# RP2040.net
KiCad netlist of a schematic drawn in Altium Designer
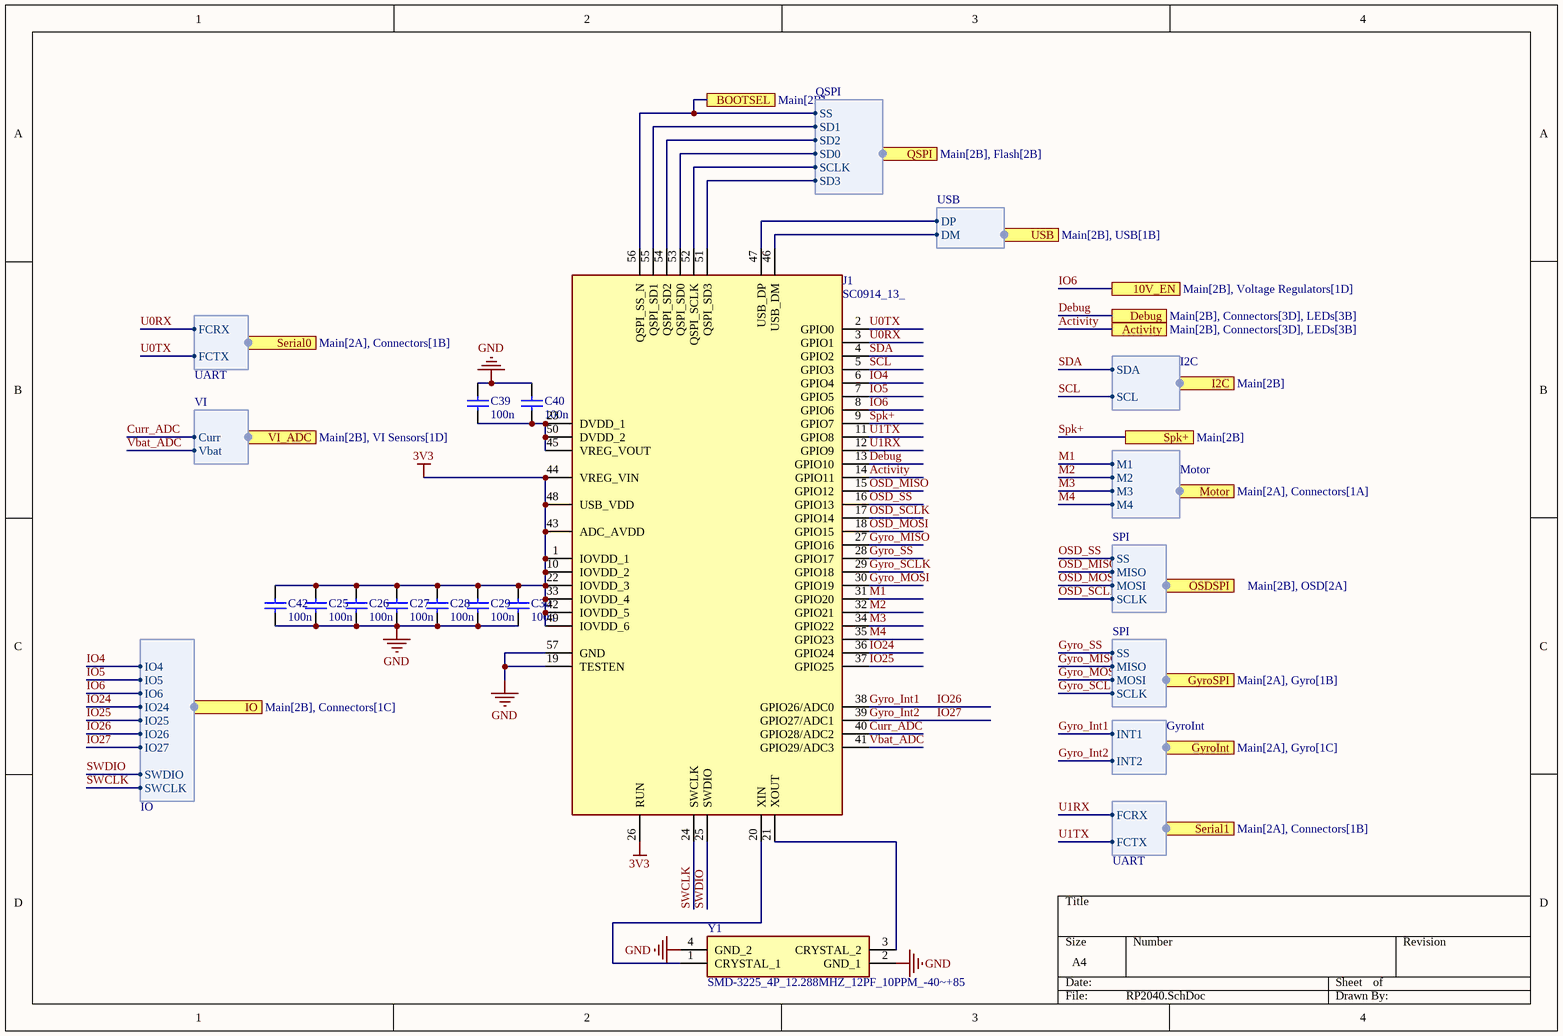
[diagram p0: RP2040.SchDoc]

(export (version "E")
  (design (tool "Eeschema 10.0.6"))
  (components
    (comp (ref "C25")
      (value "100n")
      (footprint "CAPC0603(1608)55_N")
      (description "Keramikvielschichtkondensator, SMD, Baureihe MC, ± 20%")
      (fields (field (name "MANUFACTURER") "Multicomp"))
      (libsource (lib "Standardbauteile") (part "Cap 100n"))
    )
    (comp (ref "C26")
      (value "100n")
      (footprint "CAPC0603(1608)55_N")
      (description "Keramikvielschichtkondensator, SMD, Baureihe MC, ± 20%")
      (fields (field (name "MANUFACTURER") "Multicomp"))
      (libsource (lib "Standardbauteile") (part "Cap 100n"))
    )
    (comp (ref "C27")
      (value "100n")
      (footprint "CAPC0603(1608)55_N")
      (description "Keramikvielschichtkondensator, SMD, Baureihe MC, ± 20%")
      (fields (field (name "MANUFACTURER") "Multicomp"))
      (libsource (lib "Standardbauteile") (part "Cap 100n"))
    )
    (comp (ref "C28")
      (value "100n")
      (footprint "CAPC0603(1608)55_N")
      (description "Keramikvielschichtkondensator, SMD, Baureihe MC, ± 20%")
      (fields (field (name "MANUFACTURER") "Multicomp"))
      (libsource (lib "Standardbauteile") (part "Cap 100n"))
    )
    (comp (ref "C29")
      (value "100n")
      (footprint "CAPC0603(1608)55_N")
      (description "Keramikvielschichtkondensator, SMD, Baureihe MC, ± 20%")
      (fields (field (name "MANUFACTURER") "Multicomp"))
      (libsource (lib "Standardbauteile") (part "Cap 100n"))
    )
    (comp (ref "C30")
      (value "100n")
      (footprint "CAPC0603(1608)55_N")
      (description "Keramikvielschichtkondensator, SMD, Baureihe MC, ± 20%")
      (fields (field (name "MANUFACTURER") "Multicomp"))
      (libsource (lib "Standardbauteile") (part "Cap 100n"))
    )
    (comp (ref "C39")
      (value "100n")
      (footprint "CAPC0603(1608)55_N")
      (description "Keramikvielschichtkondensator, SMD, Baureihe MC, ± 20%")
      (fields (field (name "MANUFACTURER") "Multicomp"))
      (libsource (lib "Standardbauteile") (part "Cap 100n"))
    )
    (comp (ref "C40")
      (value "100n")
      (footprint "CAPC0603(1608)55_N")
      (description "Keramikvielschichtkondensator, SMD, Baureihe MC, ± 20%")
      (fields (field (name "MANUFACTURER") "Multicomp"))
      (libsource (lib "Standardbauteile") (part "Cap 100n"))
    )
    (comp (ref "C42")
      (value "100n")
      (footprint "CAPC0603(1608)55_N")
      (description "Keramikvielschichtkondensator, SMD, Baureihe MC, ± 20%")
      (fields (field (name "MANUFACTURER") "Multicomp"))
      (libsource (lib "Standardbauteile") (part "Cap 100n"))
    )
    (comp (ref "J1")
      (value "SC0914_13_")
      (footprint "Custom Components:SC091413")
      (description "Connector")
      (fields
        (field (name "MANUFACTURER_PART_NUMBER") "SC0914(13)")
        (field (name "MOUSER PART NUMBER") "358-SC091413")
      )
      (libsource (lib "Custom Components") (part "SC0914_13_"))
    )
    (comp (ref "Y1")
      (value "SMD-3225_4P_12.288MHZ_12PF_10PPM_-40~+85")
      (footprint "Custom Components:SMD3225_4P12288MHZ12PF10PPM4085")
      (description "Crystal or Oscillator")
      (fields (field (name "MANUFACTURER_PART_NUMBER") "SMD-3225_4P 12.288MHZ 12PF 10PPM -40~+85℃"))
      (libsource (lib "*") (part "SMD-3225_4P_12.288MHZ_12PF_10PPM_-40~+85"))
    )
  )
  (nets
    (net (code "10") (name "/Activity") (class "Default")
      (node (ref "J1") (pin "14") (pinfunction "GPIO11_14") (pintype "passive"))
    )
    (net (code "11") (name "/BOOTSEL") (class "Default")
      (node (ref "J1") (pin "56") (pinfunction "QSPI_SS_N_56") (pintype "passive"))
    )
    (net (code "12") (name "/Curr_ADC") (class "Default")
      (node (ref "J1") (pin "40") (pinfunction "GPIO28/ADC2_40") (pintype "passive"))
    )
    (net (code "13") (name "/DM") (class "Default")
      (node (ref "J1") (pin "46") (pinfunction "USB_DM_46") (pintype "passive"))
    )
    (net (code "14") (name "/DP") (class "Default")
      (node (ref "J1") (pin "47") (pinfunction "USB_DP_47") (pintype "passive"))
    )
    (net (code "15") (name "/Debug") (class "Default")
      (node (ref "J1") (pin "13") (pinfunction "GPIO10_13") (pintype "passive"))
    )
    (net (code "16") (name "/Gyro_Int1") (class "Default")
      (node (ref "J1") (pin "38") (pinfunction "GPIO26/ADC0_38") (pintype "passive"))
    )
    (net (code "17") (name "/Gyro_Int2") (class "Default")
      (node (ref "J1") (pin "39") (pinfunction "GPIO27/ADC1_39") (pintype "passive"))
    )
    (net (code "18") (name "/Gyro_MISO") (class "Default")
      (node (ref "J1") (pin "27") (pinfunction "GPIO16_27") (pintype "passive"))
    )
    (net (code "19") (name "/Gyro_MOSI") (class "Default")
      (node (ref "J1") (pin "30") (pinfunction "GPIO19_30") (pintype "passive"))
    )
    (net (code "20") (name "/Gyro_SCLK") (class "Default")
      (node (ref "J1") (pin "29") (pinfunction "GPIO18_29") (pintype "passive"))
    )
    (net (code "21") (name "/Gyro_SS") (class "Default")
      (node (ref "J1") (pin "28") (pinfunction "GPIO17_28") (pintype "passive"))
    )
    (net (code "22") (name "/IO4") (class "Default")
      (node (ref "J1") (pin "6") (pinfunction "GPIO4_6") (pintype "passive"))
    )
    (net (code "23") (name "/IO5") (class "Default")
      (node (ref "J1") (pin "7") (pinfunction "GPIO5_7") (pintype "passive"))
    )
    (net (code "24") (name "/IO6") (class "Default")
      (node (ref "J1") (pin "8") (pinfunction "GPIO6_8") (pintype "passive"))
    )
    (net (code "25") (name "/IO24") (class "Default")
      (node (ref "J1") (pin "36") (pinfunction "GPIO24_36") (pintype "passive"))
    )
    (net (code "26") (name "/IO25") (class "Default")
      (node (ref "J1") (pin "37") (pinfunction "GPIO25_37") (pintype "passive"))
    )
    (net (code "27") (name "/M1") (class "Default")
      (node (ref "J1") (pin "31") (pinfunction "GPIO20_31") (pintype "passive"))
    )
    (net (code "28") (name "/M2") (class "Default")
      (node (ref "J1") (pin "32") (pinfunction "GPIO21_32") (pintype "passive"))
    )
    (net (code "29") (name "/M3") (class "Default")
      (node (ref "J1") (pin "34") (pinfunction "GPIO22_34") (pintype "passive"))
    )
    (net (code "30") (name "/M4") (class "Default")
      (node (ref "J1") (pin "35") (pinfunction "GPIO23_35") (pintype "passive"))
    )
    (net (code "31") (name "/OSD_MISO") (class "Default")
      (node (ref "J1") (pin "15") (pinfunction "GPIO12_15") (pintype "passive"))
    )
    (net (code "32") (name "/OSD_MOSI") (class "Default")
      (node (ref "J1") (pin "18") (pinfunction "GPIO15_18") (pintype "passive"))
    )
    (net (code "33") (name "/OSD_SCLK") (class "Default")
      (node (ref "J1") (pin "17") (pinfunction "GPIO14_17") (pintype "passive"))
    )
    (net (code "34") (name "/OSD_SS") (class "Default")
      (node (ref "J1") (pin "16") (pinfunction "GPIO13_16") (pintype "passive"))
    )
    (net (code "35") (name "/SCL") (class "Default")
      (node (ref "J1") (pin "5") (pinfunction "GPIO3_5") (pintype "passive"))
    )
    (net (code "36") (name "/SD0") (class "Default")
      (node (ref "J1") (pin "53") (pinfunction "QSPI_SD0_53") (pintype "passive"))
    )
    (net (code "37") (name "/SD1") (class "Default")
      (node (ref "J1") (pin "55") (pinfunction "QSPI_SD1_55") (pintype "passive"))
    )
    (net (code "38") (name "/SD2") (class "Default")
      (node (ref "J1") (pin "54") (pinfunction "QSPI_SD2_54") (pintype "passive"))
    )
    (net (code "39") (name "/SD3") (class "Default")
      (node (ref "J1") (pin "51") (pinfunction "QSPI_SD3_51") (pintype "passive"))
    )
    (net (code "40") (name "/SDA") (class "Default")
      (node (ref "J1") (pin "4") (pinfunction "GPIO2_4") (pintype "passive"))
    )
    (net (code "41") (name "/SWCLK") (class "Default")
      (node (ref "J1") (pin "24") (pinfunction "SWCLK_24") (pintype "passive"))
    )
    (net (code "42") (name "/SWDIO") (class "Default")
      (node (ref "J1") (pin "25") (pinfunction "SWDIO_25") (pintype "passive"))
    )
    (net (code "43") (name "/Spk+") (class "Default")
      (node (ref "J1") (pin "9") (pinfunction "GPIO7_9") (pintype "passive"))
    )
    (net (code "44") (name "/U0RX") (class "Default")
      (node (ref "J1") (pin "3") (pinfunction "GPIO1_3") (pintype "passive"))
    )
    (net (code "45") (name "/U0TX") (class "Default")
      (node (ref "J1") (pin "2") (pinfunction "GPIO0_2") (pintype "passive"))
    )
    (net (code "46") (name "/U1RX") (class "Default")
      (node (ref "J1") (pin "12") (pinfunction "GPIO9_12") (pintype "passive"))
    )
    (net (code "47") (name "/U1TX") (class "Default")
      (node (ref "J1") (pin "11") (pinfunction "GPIO8_11") (pintype "passive"))
    )
    (net (code "48") (name "/Vbat_ADC") (class "Default")
      (node (ref "J1") (pin "41") (pinfunction "GPIO29/ADC3_41") (pintype "passive"))
    )
    (net (code "58") (name "3V3") (class "Default")
      (node (ref "C25") (pin "2") (pinfunction "2_2") (pintype "passive"))
      (node (ref "C26") (pin "2") (pinfunction "2_2") (pintype "passive"))
      (node (ref "C27") (pin "2") (pinfunction "2_2") (pintype "passive"))
      (node (ref "C28") (pin "2") (pinfunction "2_2") (pintype "passive"))
      (node (ref "C29") (pin "2") (pinfunction "2_2") (pintype "passive"))
      (node (ref "C30") (pin "2") (pinfunction "2_2") (pintype "passive"))
      (node (ref "C42") (pin "2") (pinfunction "2_2") (pintype "passive"))
      (node (ref "J1") (pin "1") (pinfunction "IOVDD_1_1") (pintype "passive"))
      (node (ref "J1") (pin "10") (pinfunction "IOVDD_2_10") (pintype "passive"))
      (node (ref "J1") (pin "22") (pinfunction "IOVDD_3_22") (pintype "passive"))
      (node (ref "J1") (pin "26") (pinfunction "RUN_26") (pintype "passive"))
      (node (ref "J1") (pin "33") (pinfunction "IOVDD_4_33") (pintype "passive"))
      (node (ref "J1") (pin "42") (pinfunction "IOVDD_5_42") (pintype "passive"))
      (node (ref "J1") (pin "43") (pinfunction "ADC_AVDD_43") (pintype "passive"))
      (node (ref "J1") (pin "44") (pinfunction "VREG_VIN_44") (pintype "passive"))
      (node (ref "J1") (pin "48") (pinfunction "USB_VDD_48") (pintype "passive"))
      (node (ref "J1") (pin "49") (pinfunction "IOVDD_6_49") (pintype "passive"))
    )
    (net (code "59") (name "GND") (class "Default")
      (node (ref "C25") (pin "1") (pinfunction "1_1") (pintype "passive"))
      (node (ref "C26") (pin "1") (pinfunction "1_1") (pintype "passive"))
      (node (ref "C27") (pin "1") (pinfunction "1_1") (pintype "passive"))
      (node (ref "C28") (pin "1") (pinfunction "1_1") (pintype "passive"))
      (node (ref "C29") (pin "1") (pinfunction "1_1") (pintype "passive"))
      (node (ref "C30") (pin "1") (pinfunction "1_1") (pintype "passive"))
      (node (ref "C39") (pin "2") (pinfunction "2_2") (pintype "passive"))
      (node (ref "C40") (pin "2") (pinfunction "2_2") (pintype "passive"))
      (node (ref "C42") (pin "1") (pinfunction "1_1") (pintype "passive"))
      (node (ref "J1") (pin "19") (pinfunction "TESTEN_19") (pintype "passive"))
      (node (ref "J1") (pin "57") (pinfunction "GND_57") (pintype "passive"))
      (node (ref "Y1") (pin "2") (pinfunction "GND_1_2") (pintype "passive"))
      (node (ref "Y1") (pin "4") (pinfunction "GND_2_4") (pintype "passive"))
    )
    (net (code "60") (name "Net-(J1-DVDD_1)") (class "Default")
      (node (ref "C39") (pin "1") (pinfunction "1_1") (pintype "passive"))
      (node (ref "C40") (pin "1") (pinfunction "1_1") (pintype "passive"))
      (node (ref "J1") (pin "23") (pinfunction "DVDD_1_23") (pintype "passive"))
      (node (ref "J1") (pin "45") (pinfunction "VREG_VOUT_45") (pintype "passive"))
      (node (ref "J1") (pin "50") (pinfunction "DVDD_2_50") (pintype "passive"))
    )
    (net (code "61") (name "Net-(J1-XIN)") (class "Default")
      (node (ref "J1") (pin "20") (pinfunction "XIN_20") (pintype "passive"))
      (node (ref "Y1") (pin "1") (pinfunction "CRYSTAL_1_1") (pintype "passive"))
    )
    (net (code "62") (name "Net-(J1-XOUT)") (class "Default")
      (node (ref "J1") (pin "21") (pinfunction "XOUT_21") (pintype "passive"))
      (node (ref "Y1") (pin "3") (pinfunction "CRYSTAL_2_3") (pintype "passive"))
    )
    (net (code "63") (name "unconnected-(J1-QSPI_SCLK-Pad52)") (class "Default")
      (node (ref "J1") (pin "52") (pinfunction "QSPI_SCLK_52") (pintype "passive"))
    )
  )
)
